# automotive-mirror-microcontroller-compon.net
KiCad netlist of a schematic drawn in Altium Designer
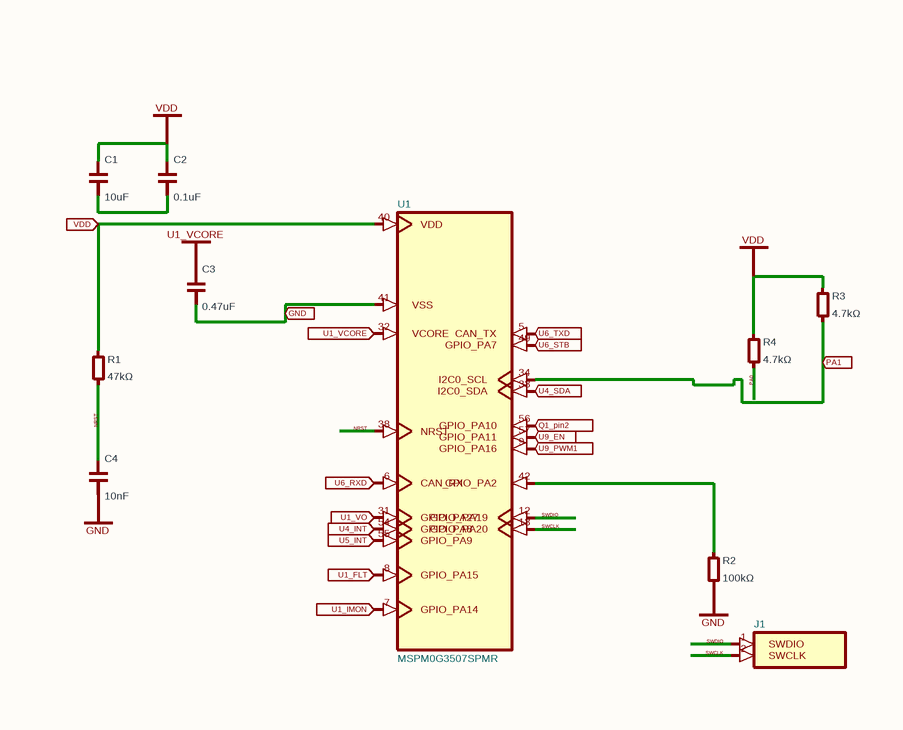
[diagram p0: automotive-mirror-microcontroller-component-text-4pt.SchDoc]

(export (version "E")
  (design (tool "Eeschema 10.0.6"))
  (components
    (comp (ref "C1") (value "10uF") (libsource (lib "altium-import") (part "root_0_capacitor_down_")))
    (comp (ref "C2") (value "0.1uF") (libsource (lib "altium-import") (part "root_0_capacitor_down_")))
    (comp (ref "C3") (value "0.47uF") (libsource (lib "altium-import") (part "root_0_capacitor_down_")))
    (comp (ref "C4") (value "10nF") (libsource (lib "altium-import") (part "root_0_capacitor_down_")))
    (comp (ref "J1") (value "~") (libsource (lib "altium-import") (part "root_0_J1_")))
    (comp (ref "R1") (value "47kΩ") (libsource (lib "altium-import") (part "root_0_boxresistor_up_")))
    (comp (ref "R2") (value "100kΩ") (libsource (lib "altium-import") (part "root_0_boxresistor_down_")))
    (comp (ref "R3") (value "4.7kΩ") (libsource (lib "altium-import") (part "root_0_boxresistor_up_")))
    (comp (ref "R4") (value "4.7kΩ") (libsource (lib "altium-import") (part "root_0_boxresistor_up_")))
    (comp (ref "U1") (value "~") (libsource (lib "altium-import") (part "root_0_U1_")))
  )
  (nets
    (net (code "1") (name "/PA1") (class "Default")
      (node (ref "R3") (pin "1") (pinfunction "anode_1") (pintype "input"))
      (node (ref "U1") (pin "34") (pinfunction "I2C0_SCL_34") (pintype "input"))
    )
    (net (code "2") (name "/Q1_pin2") (class "Default")
      (node (ref "U1") (pin "56") (pinfunction "GPIO_PA10_56") (pintype "input"))
    )
    (net (code "3") (name "/U1_FLT") (class "Default")
      (node (ref "U1") (pin "8") (pinfunction "GPIO_PA15_8") (pintype "input"))
    )
    (net (code "4") (name "/U1_IMON") (class "Default")
      (node (ref "U1") (pin "7") (pinfunction "GPIO_PA14_7") (pintype "input"))
    )
    (net (code "5") (name "/U1_VO") (class "Default")
      (node (ref "U1") (pin "31") (pinfunction "GPIO_PA27_31") (pintype "input"))
    )
    (net (code "6") (name "/U4_INT") (class "Default")
      (node (ref "U1") (pin "54") (pinfunction "GPIO_PA8_54") (pintype "input"))
    )
    (net (code "7") (name "/U4_SDA") (class "Default")
      (node (ref "U1") (pin "33") (pinfunction "I2C0_SDA_33") (pintype "input"))
    )
    (net (code "8") (name "/U5_INT") (class "Default")
      (node (ref "U1") (pin "55") (pinfunction "GPIO_PA9_55") (pintype "input"))
    )
    (net (code "9") (name "/U6_RXD") (class "Default")
      (node (ref "U1") (pin "6") (pinfunction "CAN_RX_6") (pintype "input"))
    )
    (net (code "10") (name "/U6_STB") (class "Default")
      (node (ref "U1") (pin "49") (pinfunction "GPIO_PA7_49") (pintype "input"))
    )
    (net (code "11") (name "/U6_TXD") (class "Default")
      (node (ref "U1") (pin "5") (pinfunction "CAN_TX_5") (pintype "input"))
    )
    (net (code "12") (name "/U9_EN") (class "Default")
      (node (ref "U1") (pin "57") (pinfunction "GPIO_PA11_57") (pintype "input"))
    )
    (net (code "13") (name "/U9_PWM1") (class "Default")
      (node (ref "U1") (pin "9") (pinfunction "GPIO_PA16_9") (pintype "input"))
    )
    (net (code "14") (name "GND") (class "Default")
      (node (ref "C3") (pin "2") (pinfunction "cathode_2") (pintype "input"))
      (node (ref "C4") (pin "2") (pinfunction "cathode_2") (pintype "input"))
      (node (ref "R2") (pin "2") (pinfunction "cathode_2") (pintype "input"))
      (node (ref "U1") (pin "41") (pinfunction "VSS_41") (pintype "input"))
    )
    (net (code "15") (name "Net-(C1-cathode)") (class "Default")
      (node (ref "C1") (pin "2") (pinfunction "cathode_2") (pintype "input"))
      (node (ref "C2") (pin "2") (pinfunction "cathode_2") (pintype "input"))
    )
    (net (code "16") (name "Net-(C4-anode)") (class "Default")
      (node (ref "C4") (pin "1") (pinfunction "anode_1") (pintype "input"))
      (node (ref "R1") (pin "1") (pinfunction "anode_1") (pintype "input"))
    )
    (net (code "17") (name "Net-(R2-anode)") (class "Default")
      (node (ref "R2") (pin "1") (pinfunction "anode_1") (pintype "input"))
      (node (ref "U1") (pin "42") (pinfunction "GPIO_PA2_42") (pintype "input"))
    )
    (net (code "18") (name "U1_VCORE") (class "Default")
      (node (ref "C3") (pin "1") (pinfunction "anode_1") (pintype "input"))
      (node (ref "U1") (pin "32") (pinfunction "VCORE_32") (pintype "input"))
    )
    (net (code "19") (name "VDD") (class "Default")
      (node (ref "C1") (pin "1") (pinfunction "anode_1") (pintype "input"))
      (node (ref "C2") (pin "1") (pinfunction "anode_1") (pintype "input"))
      (node (ref "R1") (pin "2") (pinfunction "cathode_2") (pintype "input"))
      (node (ref "R3") (pin "2") (pinfunction "cathode_2") (pintype "input"))
      (node (ref "R4") (pin "2") (pinfunction "cathode_2") (pintype "input"))
      (node (ref "U1") (pin "40") (pinfunction "VDD_40") (pintype "input"))
    )
    (net (code "20") (name "unconnected-(J1-SWCLK-Pad2)") (class "Default")
      (node (ref "J1") (pin "2") (pinfunction "SWCLK_2") (pintype "input"))
    )
    (net (code "21") (name "unconnected-(J1-SWDIO-Pad1)") (class "Default")
      (node (ref "J1") (pin "1") (pinfunction "SWDIO_1") (pintype "input"))
    )
    (net (code "22") (name "unconnected-(R4-anode-Pad1)") (class "Default")
      (node (ref "R4") (pin "1") (pinfunction "anode_1") (pintype "input"))
    )
    (net (code "23") (name "unconnected-(U1-GPIO_PA19-Pad12)") (class "Default")
      (node (ref "U1") (pin "12") (pinfunction "GPIO_PA19_12") (pintype "input"))
    )
    (net (code "24") (name "unconnected-(U1-GPIO_PA20-Pad13)") (class "Default")
      (node (ref "U1") (pin "13") (pinfunction "GPIO_PA20_13") (pintype "input"))
    )
    (net (code "25") (name "unconnected-(U1-NRST-Pad38)") (class "Default")
      (node (ref "U1") (pin "38") (pinfunction "NRST_38") (pintype "input"))
    )
  )
)
